# LEDs.net
KiCad netlist of a schematic drawn in Altium Designer
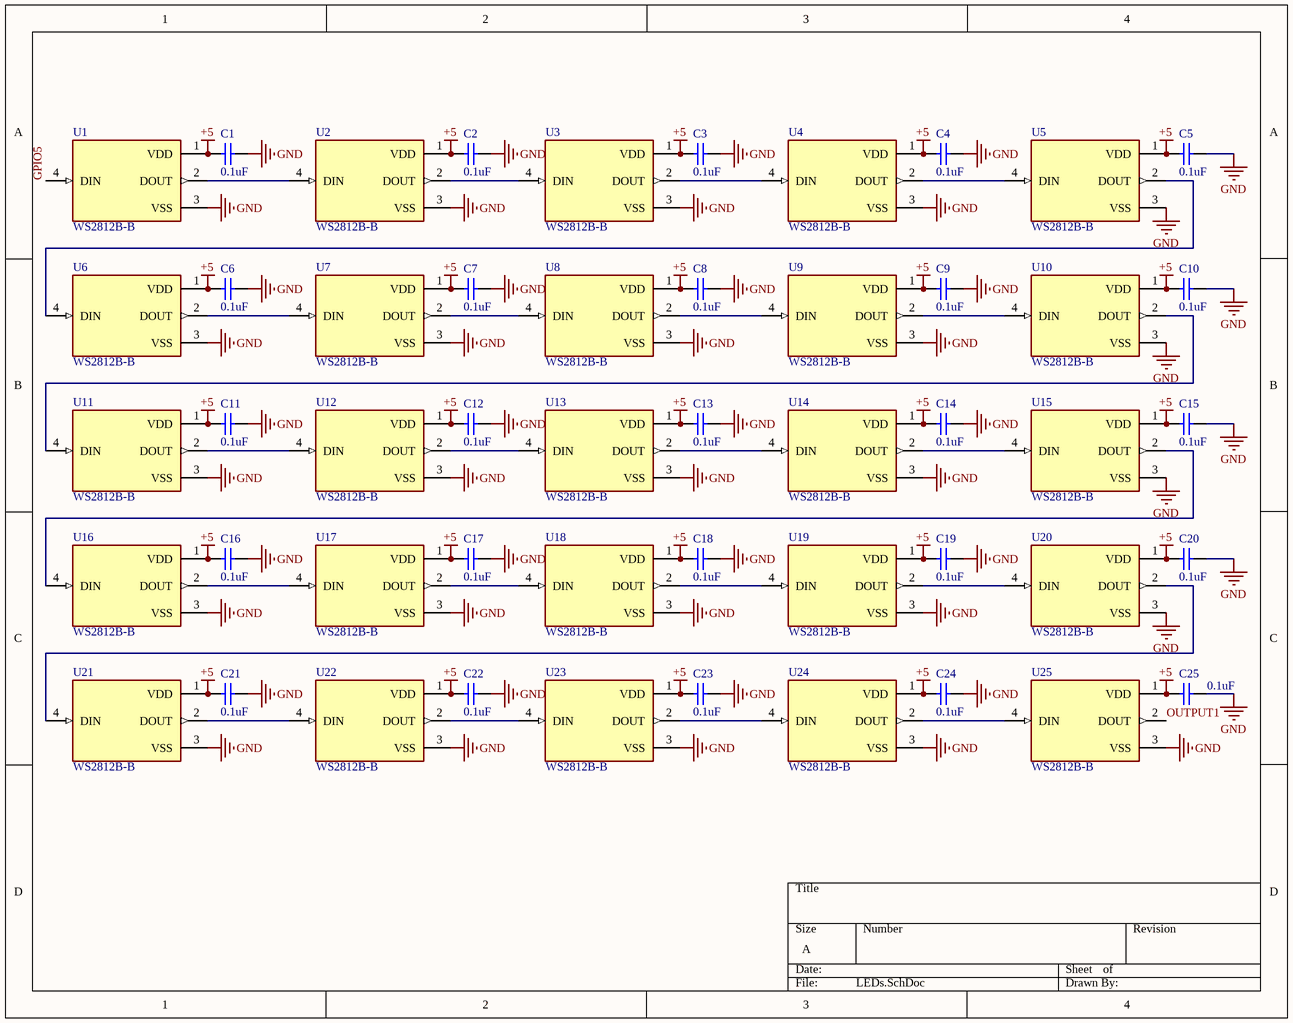
[diagram p0: LEDs.SchDoc]

(export (version "E")
  (design (tool "Eeschema 10.0.6"))
  (components
    (comp (ref "C1")
      (value "0.1uF")
      (footprint "CAPC3413X12N")
      (description "CAP 0805")
      (fields (field (name "DESIGNER") "Abbas Basereh"))
      (libsource (lib "Altium") (part "CAP SMD 0805"))
    )
    (comp (ref "C2")
      (value "0.1uF")
      (footprint "CAPC3413X12N")
      (description "CAP 0805")
      (fields (field (name "DESIGNER") "Abbas Basereh"))
      (libsource (lib "Altium") (part "CAP SMD 0805"))
    )
    (comp (ref "C3")
      (value "0.1uF")
      (footprint "CAPC3413X12N")
      (description "CAP 0805")
      (fields (field (name "DESIGNER") "Abbas Basereh"))
      (libsource (lib "Altium") (part "CAP SMD 0805"))
    )
    (comp (ref "C4")
      (value "0.1uF")
      (footprint "CAPC3413X12N")
      (description "CAP 0805")
      (fields (field (name "DESIGNER") "Abbas Basereh"))
      (libsource (lib "Altium") (part "CAP SMD 0805"))
    )
    (comp (ref "C5")
      (value "0.1uF")
      (footprint "CAPC3413X12N")
      (description "CAP 0805")
      (fields (field (name "DESIGNER") "Abbas Basereh"))
      (libsource (lib "Altium") (part "CAP SMD 0805"))
    )
    (comp (ref "C6")
      (value "0.1uF")
      (footprint "CAPC3413X12N")
      (description "CAP 0805")
      (fields (field (name "DESIGNER") "Abbas Basereh"))
      (libsource (lib "Altium") (part "CAP SMD 0805"))
    )
    (comp (ref "C7")
      (value "0.1uF")
      (footprint "CAPC3413X12N")
      (description "CAP 0805")
      (fields (field (name "DESIGNER") "Abbas Basereh"))
      (libsource (lib "Altium") (part "CAP SMD 0805"))
    )
    (comp (ref "C8")
      (value "0.1uF")
      (footprint "CAPC3413X12N")
      (description "CAP 0805")
      (fields (field (name "DESIGNER") "Abbas Basereh"))
      (libsource (lib "Altium") (part "CAP SMD 0805"))
    )
    (comp (ref "C9")
      (value "0.1uF")
      (footprint "CAPC3413X12N")
      (description "CAP 0805")
      (fields (field (name "DESIGNER") "Abbas Basereh"))
      (libsource (lib "Altium") (part "CAP SMD 0805"))
    )
    (comp (ref "C10")
      (value "0.1uF")
      (footprint "CAPC3413X12N")
      (description "CAP 0805")
      (fields (field (name "DESIGNER") "Abbas Basereh"))
      (libsource (lib "Altium") (part "CAP SMD 0805"))
    )
    (comp (ref "C11")
      (value "0.1uF")
      (footprint "CAPC3413X12N")
      (description "CAP 0805")
      (fields (field (name "DESIGNER") "Abbas Basereh"))
      (libsource (lib "Altium") (part "CAP SMD 0805"))
    )
    (comp (ref "C12")
      (value "0.1uF")
      (footprint "CAPC3413X12N")
      (description "CAP 0805")
      (fields (field (name "DESIGNER") "Abbas Basereh"))
      (libsource (lib "Altium") (part "CAP SMD 0805"))
    )
    (comp (ref "C13")
      (value "0.1uF")
      (footprint "CAPC3413X12N")
      (description "CAP 0805")
      (fields (field (name "DESIGNER") "Abbas Basereh"))
      (libsource (lib "Altium") (part "CAP SMD 0805"))
    )
    (comp (ref "C14")
      (value "0.1uF")
      (footprint "CAPC3413X12N")
      (description "CAP 0805")
      (fields (field (name "DESIGNER") "Abbas Basereh"))
      (libsource (lib "Altium") (part "CAP SMD 0805"))
    )
    (comp (ref "C15")
      (value "0.1uF")
      (footprint "CAPC3413X12N")
      (description "CAP 0805")
      (fields (field (name "DESIGNER") "Abbas Basereh"))
      (libsource (lib "Altium") (part "CAP SMD 0805"))
    )
    (comp (ref "C16")
      (value "0.1uF")
      (footprint "CAPC3413X12N")
      (description "CAP 0805")
      (fields (field (name "DESIGNER") "Abbas Basereh"))
      (libsource (lib "Altium") (part "CAP SMD 0805"))
    )
    (comp (ref "C17")
      (value "0.1uF")
      (footprint "CAPC3413X12N")
      (description "CAP 0805")
      (fields (field (name "DESIGNER") "Abbas Basereh"))
      (libsource (lib "Altium") (part "CAP SMD 0805"))
    )
    (comp (ref "C18")
      (value "0.1uF")
      (footprint "CAPC3413X12N")
      (description "CAP 0805")
      (fields (field (name "DESIGNER") "Abbas Basereh"))
      (libsource (lib "Altium") (part "CAP SMD 0805"))
    )
    (comp (ref "C19")
      (value "0.1uF")
      (footprint "CAPC3413X12N")
      (description "CAP 0805")
      (fields (field (name "DESIGNER") "Abbas Basereh"))
      (libsource (lib "Altium") (part "CAP SMD 0805"))
    )
    (comp (ref "C20")
      (value "0.1uF")
      (footprint "CAPC3413X12N")
      (description "CAP 0805")
      (fields (field (name "DESIGNER") "Abbas Basereh"))
      (libsource (lib "Altium") (part "CAP SMD 0805"))
    )
    (comp (ref "C21")
      (value "0.1uF")
      (footprint "CAPC3413X12N")
      (description "CAP 0805")
      (fields (field (name "DESIGNER") "Abbas Basereh"))
      (libsource (lib "Altium") (part "CAP SMD 0805"))
    )
    (comp (ref "C22")
      (value "0.1uF")
      (footprint "CAPC3413X12N")
      (description "CAP 0805")
      (fields (field (name "DESIGNER") "Abbas Basereh"))
      (libsource (lib "Altium") (part "CAP SMD 0805"))
    )
    (comp (ref "C23")
      (value "0.1uF")
      (footprint "CAPC3413X12N")
      (description "CAP 0805")
      (fields (field (name "DESIGNER") "Abbas Basereh"))
      (libsource (lib "Altium") (part "CAP SMD 0805"))
    )
    (comp (ref "C24")
      (value "0.1uF")
      (footprint "CAPC3413X12N")
      (description "CAP 0805")
      (fields (field (name "DESIGNER") "Abbas Basereh"))
      (libsource (lib "Altium") (part "CAP SMD 0805"))
    )
    (comp (ref "C25")
      (value "0.1uF")
      (footprint "CAPC3413X12N")
      (description "CAP 0805")
      (fields (field (name "DESIGNER") "Abbas Basereh"))
      (libsource (lib "Altium") (part "CAP SMD 0805"))
    )
    (comp (ref "U1")
      (value "WS2812B-B")
      (footprint "LED_WS2812B-B")
      (description "Intelligent control LED integrated light source")
      (fields (field (name "MF") "Worldsemi"))
      (libsource (lib "WS2812B-B") (part "WS2812B-B"))
    )
    (comp (ref "U2")
      (value "WS2812B-B")
      (footprint "LED_WS2812B-B")
      (description "Intelligent control LED integrated light source")
      (fields (field (name "MF") "Worldsemi"))
      (libsource (lib "WS2812B-B") (part "WS2812B-B"))
    )
    (comp (ref "U3")
      (value "WS2812B-B")
      (footprint "LED_WS2812B-B")
      (description "Intelligent control LED integrated light source")
      (fields (field (name "MF") "Worldsemi"))
      (libsource (lib "WS2812B-B") (part "WS2812B-B"))
    )
    (comp (ref "U4")
      (value "WS2812B-B")
      (footprint "LED_WS2812B-B")
      (description "Intelligent control LED integrated light source")
      (fields (field (name "MF") "Worldsemi"))
      (libsource (lib "WS2812B-B") (part "WS2812B-B"))
    )
    (comp (ref "U5")
      (value "WS2812B-B")
      (footprint "LED_WS2812B-B")
      (description "Intelligent control LED integrated light source")
      (fields (field (name "MF") "Worldsemi"))
      (libsource (lib "WS2812B-B") (part "WS2812B-B"))
    )
    (comp (ref "U6")
      (value "WS2812B-B")
      (footprint "LED_WS2812B-B")
      (description "Intelligent control LED integrated light source")
      (fields (field (name "MF") "Worldsemi"))
      (libsource (lib "WS2812B-B") (part "WS2812B-B"))
    )
    (comp (ref "U7")
      (value "WS2812B-B")
      (footprint "LED_WS2812B-B")
      (description "Intelligent control LED integrated light source")
      (fields (field (name "MF") "Worldsemi"))
      (libsource (lib "WS2812B-B") (part "WS2812B-B"))
    )
    (comp (ref "U8")
      (value "WS2812B-B")
      (footprint "LED_WS2812B-B")
      (description "Intelligent control LED integrated light source")
      (fields (field (name "MF") "Worldsemi"))
      (libsource (lib "WS2812B-B") (part "WS2812B-B"))
    )
    (comp (ref "U9")
      (value "WS2812B-B")
      (footprint "LED_WS2812B-B")
      (description "Intelligent control LED integrated light source")
      (fields (field (name "MF") "Worldsemi"))
      (libsource (lib "WS2812B-B") (part "WS2812B-B"))
    )
    (comp (ref "U10")
      (value "WS2812B-B")
      (footprint "LED_WS2812B-B")
      (description "Intelligent control LED integrated light source")
      (fields (field (name "MF") "Worldsemi"))
      (libsource (lib "WS2812B-B") (part "WS2812B-B"))
    )
    (comp (ref "U11")
      (value "WS2812B-B")
      (footprint "LED_WS2812B-B")
      (description "Intelligent control LED integrated light source")
      (fields (field (name "MF") "Worldsemi"))
      (libsource (lib "WS2812B-B") (part "WS2812B-B"))
    )
    (comp (ref "U12")
      (value "WS2812B-B")
      (footprint "LED_WS2812B-B")
      (description "Intelligent control LED integrated light source")
      (fields (field (name "MF") "Worldsemi"))
      (libsource (lib "WS2812B-B") (part "WS2812B-B"))
    )
    (comp (ref "U13")
      (value "WS2812B-B")
      (footprint "LED_WS2812B-B")
      (description "Intelligent control LED integrated light source")
      (fields (field (name "MF") "Worldsemi"))
      (libsource (lib "WS2812B-B") (part "WS2812B-B"))
    )
    (comp (ref "U14")
      (value "WS2812B-B")
      (footprint "LED_WS2812B-B")
      (description "Intelligent control LED integrated light source")
      (fields (field (name "MF") "Worldsemi"))
      (libsource (lib "WS2812B-B") (part "WS2812B-B"))
    )
    (comp (ref "U15")
      (value "WS2812B-B")
      (footprint "LED_WS2812B-B")
      (description "Intelligent control LED integrated light source")
      (fields (field (name "MF") "Worldsemi"))
      (libsource (lib "WS2812B-B") (part "WS2812B-B"))
    )
    (comp (ref "U16")
      (value "WS2812B-B")
      (footprint "LED_WS2812B-B")
      (description "Intelligent control LED integrated light source")
      (fields (field (name "MF") "Worldsemi"))
      (libsource (lib "WS2812B-B") (part "WS2812B-B"))
    )
    (comp (ref "U17")
      (value "WS2812B-B")
      (footprint "LED_WS2812B-B")
      (description "Intelligent control LED integrated light source")
      (fields (field (name "MF") "Worldsemi"))
      (libsource (lib "WS2812B-B") (part "WS2812B-B"))
    )
    (comp (ref "U18")
      (value "WS2812B-B")
      (footprint "LED_WS2812B-B")
      (description "Intelligent control LED integrated light source")
      (fields (field (name "MF") "Worldsemi"))
      (libsource (lib "WS2812B-B") (part "WS2812B-B"))
    )
    (comp (ref "U19")
      (value "WS2812B-B")
      (footprint "LED_WS2812B-B")
      (description "Intelligent control LED integrated light source")
      (fields (field (name "MF") "Worldsemi"))
      (libsource (lib "WS2812B-B") (part "WS2812B-B"))
    )
    (comp (ref "U20")
      (value "WS2812B-B")
      (footprint "LED_WS2812B-B")
      (description "Intelligent control LED integrated light source")
      (fields (field (name "MF") "Worldsemi"))
      (libsource (lib "WS2812B-B") (part "WS2812B-B"))
    )
    (comp (ref "U21")
      (value "WS2812B-B")
      (footprint "LED_WS2812B-B")
      (description "Intelligent control LED integrated light source")
      (fields (field (name "MF") "Worldsemi"))
      (libsource (lib "WS2812B-B") (part "WS2812B-B"))
    )
    (comp (ref "U22")
      (value "WS2812B-B")
      (footprint "LED_WS2812B-B")
      (description "Intelligent control LED integrated light source")
      (fields (field (name "MF") "Worldsemi"))
      (libsource (lib "WS2812B-B") (part "WS2812B-B"))
    )
    (comp (ref "U23")
      (value "WS2812B-B")
      (footprint "LED_WS2812B-B")
      (description "Intelligent control LED integrated light source")
      (fields (field (name "MF") "Worldsemi"))
      (libsource (lib "WS2812B-B") (part "WS2812B-B"))
    )
    (comp (ref "U24")
      (value "WS2812B-B")
      (footprint "LED_WS2812B-B")
      (description "Intelligent control LED integrated light source")
      (fields (field (name "MF") "Worldsemi"))
      (libsource (lib "WS2812B-B") (part "WS2812B-B"))
    )
    (comp (ref "U25")
      (value "WS2812B-B")
      (footprint "LED_WS2812B-B")
      (description "Intelligent control LED integrated light source")
      (fields (field (name "MF") "Worldsemi"))
      (libsource (lib "WS2812B-B") (part "WS2812B-B"))
    )
  )
  (nets
    (net (code "1") (name "+5") (class "Default")
      (node (ref "C1") (pin "1") (pinfunction "1_1") (pintype "passive"))
      (node (ref "C10") (pin "1") (pinfunction "1_1") (pintype "passive"))
      (node (ref "C11") (pin "1") (pinfunction "1_1") (pintype "passive"))
      (node (ref "C12") (pin "1") (pinfunction "1_1") (pintype "passive"))
      (node (ref "C13") (pin "1") (pinfunction "1_1") (pintype "passive"))
      (node (ref "C14") (pin "1") (pinfunction "1_1") (pintype "passive"))
      (node (ref "C15") (pin "1") (pinfunction "1_1") (pintype "passive"))
      (node (ref "C16") (pin "1") (pinfunction "1_1") (pintype "passive"))
      (node (ref "C17") (pin "1") (pinfunction "1_1") (pintype "passive"))
      (node (ref "C18") (pin "1") (pinfunction "1_1") (pintype "passive"))
      (node (ref "C19") (pin "1") (pinfunction "1_1") (pintype "passive"))
      (node (ref "C2") (pin "1") (pinfunction "1_1") (pintype "passive"))
      (node (ref "C20") (pin "1") (pinfunction "1_1") (pintype "passive"))
      (node (ref "C21") (pin "1") (pinfunction "1_1") (pintype "passive"))
      (node (ref "C22") (pin "1") (pinfunction "1_1") (pintype "passive"))
      (node (ref "C23") (pin "1") (pinfunction "1_1") (pintype "passive"))
      (node (ref "C24") (pin "1") (pinfunction "1_1") (pintype "passive"))
      (node (ref "C25") (pin "1") (pinfunction "1_1") (pintype "passive"))
      (node (ref "C3") (pin "1") (pinfunction "1_1") (pintype "passive"))
      (node (ref "C4") (pin "1") (pinfunction "1_1") (pintype "passive"))
      (node (ref "C5") (pin "1") (pinfunction "1_1") (pintype "passive"))
      (node (ref "C6") (pin "1") (pinfunction "1_1") (pintype "passive"))
      (node (ref "C7") (pin "1") (pinfunction "1_1") (pintype "passive"))
      (node (ref "C8") (pin "1") (pinfunction "1_1") (pintype "passive"))
      (node (ref "C9") (pin "1") (pinfunction "1_1") (pintype "passive"))
      (node (ref "U1") (pin "1") (pinfunction "VDD_1") (pintype "power_in"))
      (node (ref "U10") (pin "1") (pinfunction "VDD_1") (pintype "power_in"))
      (node (ref "U11") (pin "1") (pinfunction "VDD_1") (pintype "power_in"))
      (node (ref "U12") (pin "1") (pinfunction "VDD_1") (pintype "power_in"))
      (node (ref "U13") (pin "1") (pinfunction "VDD_1") (pintype "power_in"))
      (node (ref "U14") (pin "1") (pinfunction "VDD_1") (pintype "power_in"))
      (node (ref "U15") (pin "1") (pinfunction "VDD_1") (pintype "power_in"))
      (node (ref "U16") (pin "1") (pinfunction "VDD_1") (pintype "power_in"))
      (node (ref "U17") (pin "1") (pinfunction "VDD_1") (pintype "power_in"))
      (node (ref "U18") (pin "1") (pinfunction "VDD_1") (pintype "power_in"))
      (node (ref "U19") (pin "1") (pinfunction "VDD_1") (pintype "power_in"))
      (node (ref "U2") (pin "1") (pinfunction "VDD_1") (pintype "power_in"))
      (node (ref "U20") (pin "1") (pinfunction "VDD_1") (pintype "power_in"))
      (node (ref "U21") (pin "1") (pinfunction "VDD_1") (pintype "power_in"))
      (node (ref "U22") (pin "1") (pinfunction "VDD_1") (pintype "power_in"))
      (node (ref "U23") (pin "1") (pinfunction "VDD_1") (pintype "power_in"))
      (node (ref "U24") (pin "1") (pinfunction "VDD_1") (pintype "power_in"))
      (node (ref "U25") (pin "1") (pinfunction "VDD_1") (pintype "power_in"))
      (node (ref "U3") (pin "1") (pinfunction "VDD_1") (pintype "power_in"))
      (node (ref "U4") (pin "1") (pinfunction "VDD_1") (pintype "power_in"))
      (node (ref "U5") (pin "1") (pinfunction "VDD_1") (pintype "power_in"))
      (node (ref "U6") (pin "1") (pinfunction "VDD_1") (pintype "power_in"))
      (node (ref "U7") (pin "1") (pinfunction "VDD_1") (pintype "power_in"))
      (node (ref "U8") (pin "1") (pinfunction "VDD_1") (pintype "power_in"))
      (node (ref "U9") (pin "1") (pinfunction "VDD_1") (pintype "power_in"))
    )
    (net (code "2") (name "/GPIO5") (class "Default")
      (node (ref "U1") (pin "4") (pinfunction "DIN_4") (pintype "input"))
    )
    (net (code "3") (name "/OUTPUT1") (class "Default")
      (node (ref "U25") (pin "2") (pinfunction "DOUT_2") (pintype "output"))
    )
    (net (code "4") (name "GND") (class "Default")
      (node (ref "C1") (pin "2") (pinfunction "2_2") (pintype "passive"))
      (node (ref "C10") (pin "2") (pinfunction "2_2") (pintype "passive"))
      (node (ref "C11") (pin "2") (pinfunction "2_2") (pintype "passive"))
      (node (ref "C12") (pin "2") (pinfunction "2_2") (pintype "passive"))
      (node (ref "C13") (pin "2") (pinfunction "2_2") (pintype "passive"))
      (node (ref "C14") (pin "2") (pinfunction "2_2") (pintype "passive"))
      (node (ref "C15") (pin "2") (pinfunction "2_2") (pintype "passive"))
      (node (ref "C16") (pin "2") (pinfunction "2_2") (pintype "passive"))
      (node (ref "C17") (pin "2") (pinfunction "2_2") (pintype "passive"))
      (node (ref "C18") (pin "2") (pinfunction "2_2") (pintype "passive"))
      (node (ref "C19") (pin "2") (pinfunction "2_2") (pintype "passive"))
      (node (ref "C2") (pin "2") (pinfunction "2_2") (pintype "passive"))
      (node (ref "C20") (pin "2") (pinfunction "2_2") (pintype "passive"))
      (node (ref "C21") (pin "2") (pinfunction "2_2") (pintype "passive"))
      (node (ref "C22") (pin "2") (pinfunction "2_2") (pintype "passive"))
      (node (ref "C23") (pin "2") (pinfunction "2_2") (pintype "passive"))
      (node (ref "C24") (pin "2") (pinfunction "2_2") (pintype "passive"))
      (node (ref "C25") (pin "2") (pinfunction "2_2") (pintype "passive"))
      (node (ref "C3") (pin "2") (pinfunction "2_2") (pintype "passive"))
      (node (ref "C4") (pin "2") (pinfunction "2_2") (pintype "passive"))
      (node (ref "C5") (pin "2") (pinfunction "2_2") (pintype "passive"))
      (node (ref "C6") (pin "2") (pinfunction "2_2") (pintype "passive"))
      (node (ref "C7") (pin "2") (pinfunction "2_2") (pintype "passive"))
      (node (ref "C8") (pin "2") (pinfunction "2_2") (pintype "passive"))
      (node (ref "C9") (pin "2") (pinfunction "2_2") (pintype "passive"))
      (node (ref "U1") (pin "3") (pinfunction "VSS_3") (pintype "power_in"))
      (node (ref "U10") (pin "3") (pinfunction "VSS_3") (pintype "power_in"))
      (node (ref "U11") (pin "3") (pinfunction "VSS_3") (pintype "power_in"))
      (node (ref "U12") (pin "3") (pinfunction "VSS_3") (pintype "power_in"))
      (node (ref "U13") (pin "3") (pinfunction "VSS_3") (pintype "power_in"))
      (node (ref "U14") (pin "3") (pinfunction "VSS_3") (pintype "power_in"))
      (node (ref "U15") (pin "3") (pinfunction "VSS_3") (pintype "power_in"))
      (node (ref "U16") (pin "3") (pinfunction "VSS_3") (pintype "power_in"))
      (node (ref "U17") (pin "3") (pinfunction "VSS_3") (pintype "power_in"))
      (node (ref "U18") (pin "3") (pinfunction "VSS_3") (pintype "power_in"))
      (node (ref "U19") (pin "3") (pinfunction "VSS_3") (pintype "power_in"))
      (node (ref "U2") (pin "3") (pinfunction "VSS_3") (pintype "power_in"))
      (node (ref "U20") (pin "3") (pinfunction "VSS_3") (pintype "power_in"))
      (node (ref "U21") (pin "3") (pinfunction "VSS_3") (pintype "power_in"))
      (node (ref "U22") (pin "3") (pinfunction "VSS_3") (pintype "power_in"))
      (node (ref "U23") (pin "3") (pinfunction "VSS_3") (pintype "power_in"))
      (node (ref "U24") (pin "3") (pinfunction "VSS_3") (pintype "power_in"))
      (node (ref "U25") (pin "3") (pinfunction "VSS_3") (pintype "power_in"))
      (node (ref "U3") (pin "3") (pinfunction "VSS_3") (pintype "power_in"))
      (node (ref "U4") (pin "3") (pinfunction "VSS_3") (pintype "power_in"))
      (node (ref "U5") (pin "3") (pinfunction "VSS_3") (pintype "power_in"))
      (node (ref "U6") (pin "3") (pinfunction "VSS_3") (pintype "power_in"))
      (node (ref "U7") (pin "3") (pinfunction "VSS_3") (pintype "power_in"))
      (node (ref "U8") (pin "3") (pinfunction "VSS_3") (pintype "power_in"))
      (node (ref "U9") (pin "3") (pinfunction "VSS_3") (pintype "power_in"))
    )
    (net (code "5") (name "Net-(U1-DOUT)") (class "Default")
      (node (ref "U1") (pin "2") (pinfunction "DOUT_2") (pintype "output"))
      (node (ref "U2") (pin "4") (pinfunction "DIN_4") (pintype "input"))
    )
    (net (code "6") (name "Net-(U2-DOUT)") (class "Default")
      (node (ref "U2") (pin "2") (pinfunction "DOUT_2") (pintype "output"))
      (node (ref "U3") (pin "4") (pinfunction "DIN_4") (pintype "input"))
    )
    (net (code "7") (name "Net-(U3-DOUT)") (class "Default")
      (node (ref "U3") (pin "2") (pinfunction "DOUT_2") (pintype "output"))
      (node (ref "U4") (pin "4") (pinfunction "DIN_4") (pintype "input"))
    )
    (net (code "8") (name "Net-(U4-DOUT)") (class "Default")
      (node (ref "U4") (pin "2") (pinfunction "DOUT_2") (pintype "output"))
      (node (ref "U5") (pin "4") (pinfunction "DIN_4") (pintype "input"))
    )
    (net (code "9") (name "Net-(U5-DOUT)") (class "Default")
      (node (ref "U5") (pin "2") (pinfunction "DOUT_2") (pintype "output"))
      (node (ref "U6") (pin "4") (pinfunction "DIN_4") (pintype "input"))
    )
    (net (code "10") (name "Net-(U6-DOUT)") (class "Default")
      (node (ref "U6") (pin "2") (pinfunction "DOUT_2") (pintype "output"))
      (node (ref "U7") (pin "4") (pinfunction "DIN_4") (pintype "input"))
    )
    (net (code "11") (name "Net-(U7-DOUT)") (class "Default")
      (node (ref "U7") (pin "2") (pinfunction "DOUT_2") (pintype "output"))
      (node (ref "U8") (pin "4") (pinfunction "DIN_4") (pintype "input"))
    )
    (net (code "12") (name "Net-(U8-DOUT)") (class "Default")
      (node (ref "U8") (pin "2") (pinfunction "DOUT_2") (pintype "output"))
      (node (ref "U9") (pin "4") (pinfunction "DIN_4") (pintype "input"))
    )
    (net (code "13") (name "Net-(U10-DIN)") (class "Default")
      (node (ref "U10") (pin "4") (pinfunction "DIN_4") (pintype "input"))
      (node (ref "U9") (pin "2") (pinfunction "DOUT_2") (pintype "output"))
    )
    (net (code "14") (name "Net-(U10-DOUT)") (class "Default")
      (node (ref "U10") (pin "2") (pinfunction "DOUT_2") (pintype "output"))
      (node (ref "U11") (pin "4") (pinfunction "DIN_4") (pintype "input"))
    )
    (net (code "15") (name "Net-(U11-DOUT)") (class "Default")
      (node (ref "U11") (pin "2") (pinfunction "DOUT_2") (pintype "output"))
      (node (ref "U12") (pin "4") (pinfunction "DIN_4") (pintype "input"))
    )
    (net (code "16") (name "Net-(U12-DOUT)") (class "Default")
      (node (ref "U12") (pin "2") (pinfunction "DOUT_2") (pintype "output"))
      (node (ref "U13") (pin "4") (pinfunction "DIN_4") (pintype "input"))
    )
    (net (code "17") (name "Net-(U13-DOUT)") (class "Default")
      (node (ref "U13") (pin "2") (pinfunction "DOUT_2") (pintype "output"))
      (node (ref "U14") (pin "4") (pinfunction "DIN_4") (pintype "input"))
    )
    (net (code "18") (name "Net-(U14-DOUT)") (class "Default")
      (node (ref "U14") (pin "2") (pinfunction "DOUT_2") (pintype "output"))
      (node (ref "U15") (pin "4") (pinfunction "DIN_4") (pintype "input"))
    )
    (net (code "19") (name "Net-(U15-DOUT)") (class "Default")
      (node (ref "U15") (pin "2") (pinfunction "DOUT_2") (pintype "output"))
      (node (ref "U16") (pin "4") (pinfunction "DIN_4") (pintype "input"))
    )
    (net (code "20") (name "Net-(U16-DOUT)") (class "Default")
      (node (ref "U16") (pin "2") (pinfunction "DOUT_2") (pintype "output"))
      (node (ref "U17") (pin "4") (pinfunction "DIN_4") (pintype "input"))
    )
    (net (code "21") (name "Net-(U17-DOUT)") (class "Default")
      (node (ref "U17") (pin "2") (pinfunction "DOUT_2") (pintype "output"))
      (node (ref "U18") (pin "4") (pinfunction "DIN_4") (pintype "input"))
    )
    (net (code "22") (name "Net-(U18-DOUT)") (class "Default")
      (node (ref "U18") (pin "2") (pinfunction "DOUT_2") (pintype "output"))
      (node (ref "U19") (pin "4") (pinfunction "DIN_4") (pintype "input"))
    )
    (net (code "23") (name "Net-(U19-DOUT)") (class "Default")
      (node (ref "U19") (pin "2") (pinfunction "DOUT_2") (pintype "output"))
      (node (ref "U20") (pin "4") (pinfunction "DIN_4") (pintype "input"))
    )
    (net (code "24") (name "Net-(U20-DOUT)") (class "Default")
      (node (ref "U20") (pin "2") (pinfunction "DOUT_2") (pintype "output"))
      (node (ref "U21") (pin "4") (pinfunction "DIN_4") (pintype "input"))
    )
    (net (code "25") (name "Net-(U21-DOUT)") (class "Default")
      (node (ref "U21") (pin "2") (pinfunction "DOUT_2") (pintype "output"))
      (node (ref "U22") (pin "4") (pinfunction "DIN_4") (pintype "input"))
    )
    (net (code "26") (name "Net-(U22-DOUT)") (class "Default")
      (node (ref "U22") (pin "2") (pinfunction "DOUT_2") (pintype "output"))
      (node (ref "U23") (pin "4") (pinfunction "DIN_4") (pintype "input"))
    )
    (net (code "27") (name "Net-(U23-DOUT)") (class "Default")
      (node (ref "U23") (pin "2") (pinfunction "DOUT_2") (pintype "output"))
      (node (ref "U24") (pin "4") (pinfunction "DIN_4") (pintype "input"))
    )
    (net (code "28") (name "Net-(U24-DOUT)") (class "Default")
      (node (ref "U24") (pin "2") (pinfunction "DOUT_2") (pintype "output"))
      (node (ref "U25") (pin "4") (pinfunction "DIN_4") (pintype "input"))
    )
  )
)
